# GPIOexpander_4.net
KiCad netlist of a schematic drawn in EAGLE
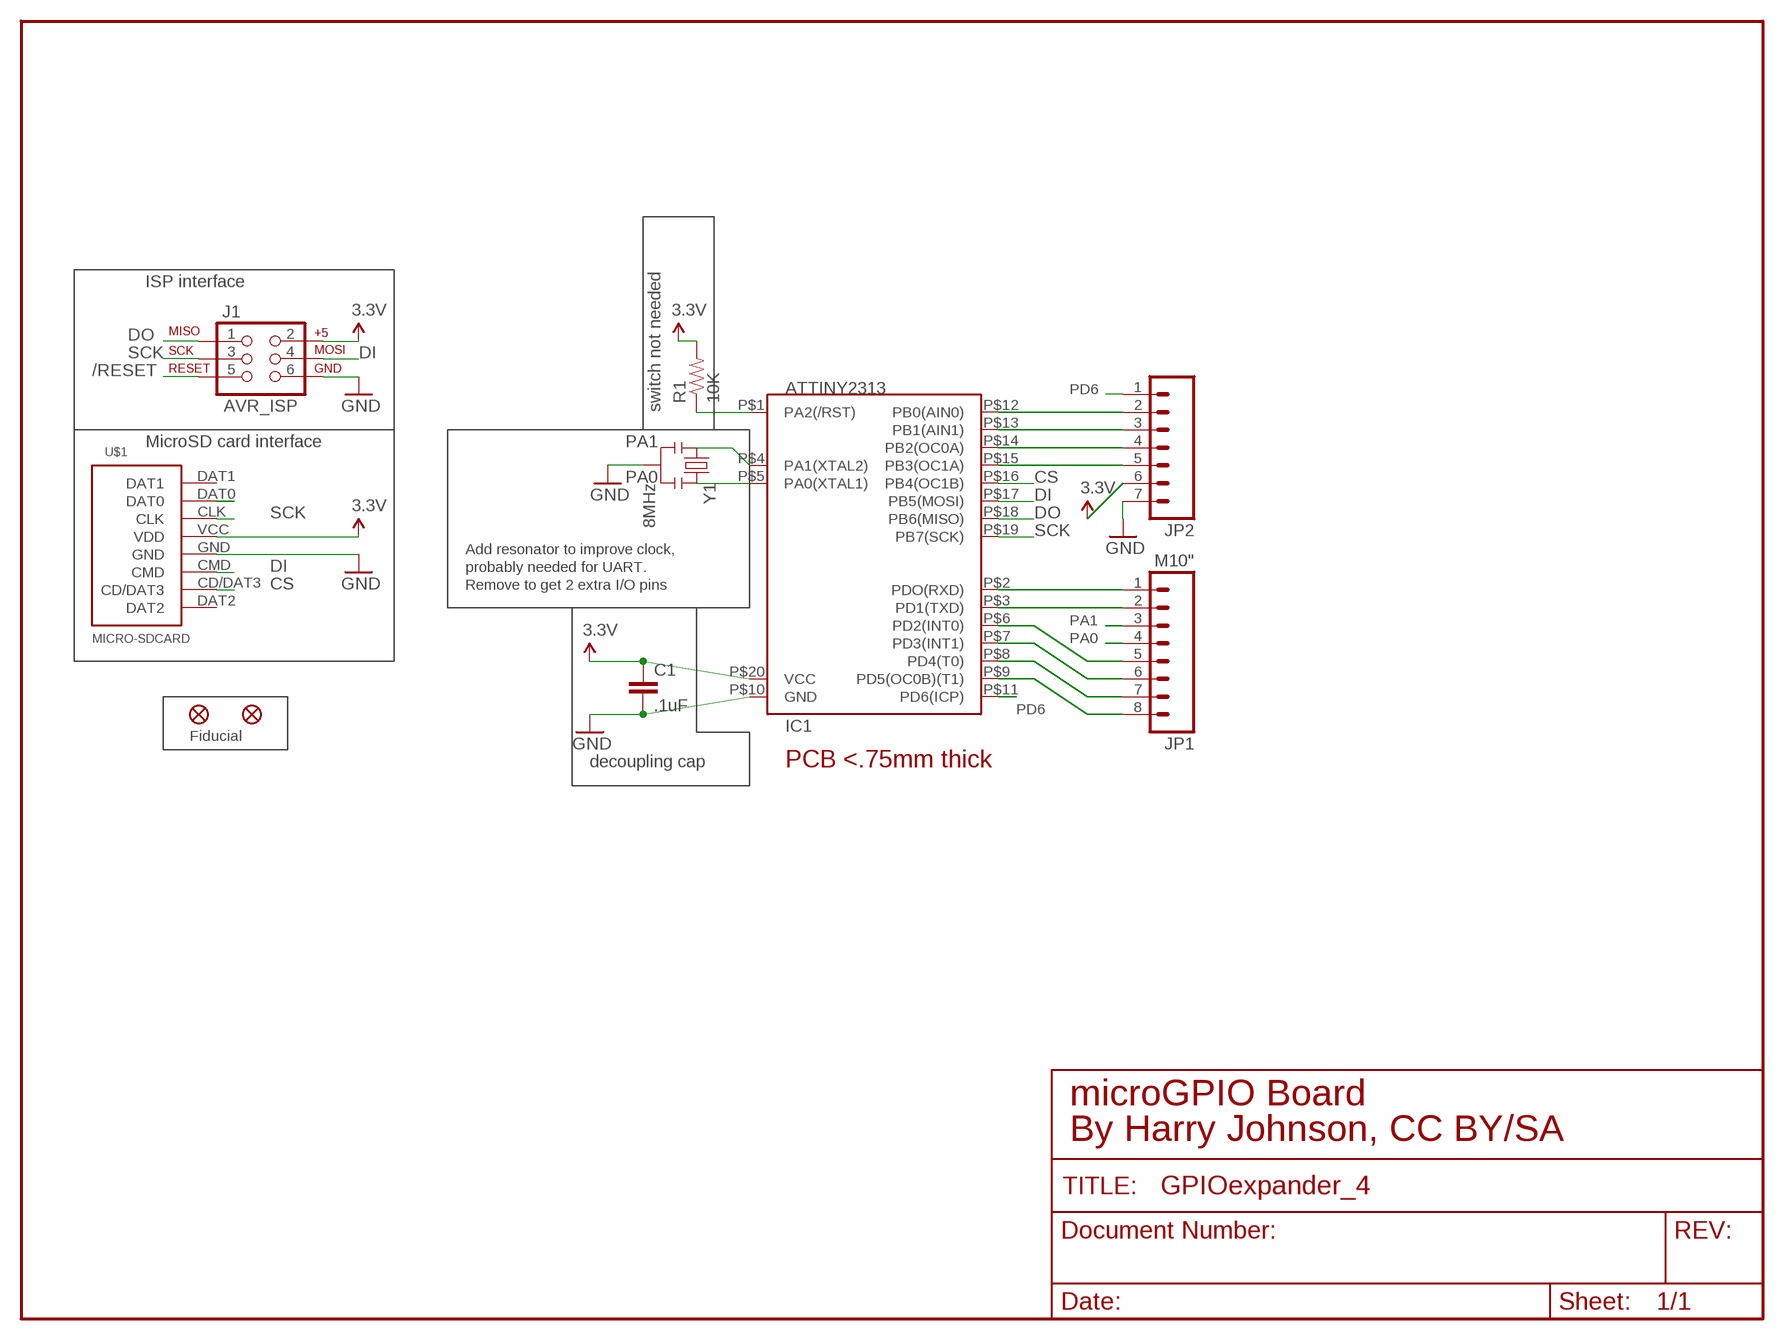
[diagram p0: schematic, sheet 1]

(export (version "E")
  (design (tool "Eeschema 10.0.6"))
  (components
    (comp (ref "C1")
      (value ".1uF")
      (footprint "eagle-import:0805")
      (libsource (lib "eagle-import") (part "CAP0805"))
    )
    (comp (ref "IC1")
      (value "ATTINY2313")
      (footprint "eagle-import:SO20W")
      (libsource (lib "eagle-import") (part "ATTINY2313SOIC"))
    )
    (comp (ref "J1")
      (value "AVR_ISP")
      (footprint "eagle-import:2X3-NS")
      (libsource (lib "eagle-import") (part "AVR_SPI_PRG_6NS"))
    )
    (comp (ref "JP1")
      (value "M10\"")
      (footprint "eagle-import:1X08")
      (libsource (lib "eagle-import") (part "M08"))
    )
    (comp (ref "JP2")
      (value "M07")
      (footprint "eagle-import:1X07")
      (libsource (lib "eagle-import") (part "M07"))
    )
    (comp (ref "R1")
      (value "10K")
      (footprint "eagle-import:0805")
      (libsource (lib "eagle-import") (part "RESISTOR"))
    )
    (comp (ref "U$1")
      (value "MICRO-SDCARD")
      (footprint "eagle-import:MICRO-SDCARD")
      (libsource (lib "eagle-import") (part "MICRO-SDCARD"))
    )
    (comp (ref "U$2")
      (value "FIDUCIAL1X2.5")
      (footprint "eagle-import:FIDUCIAL-1X2.5")
      (libsource (lib "eagle-import") (part "FIDUCIAL1X2.5"))
    )
    (comp (ref "U$3")
      (value "FIDUCIAL1X2.5")
      (footprint "eagle-import:FIDUCIAL-1X2.5")
      (libsource (lib "eagle-import") (part "FIDUCIAL1X2.5"))
    )
    (comp (ref "Y1")
      (value "8MHz")
      (footprint "eagle-import:RESONATOR-SMD")
      (libsource (lib "eagle-import") (part "RESONATORSMD"))
    )
  )
  (nets
    (net (code "1") (name "/CS") (class "Default")
      (node (ref "IC1") (pin "P$16") (pinfunction "PB4(OC1B)_P$16") (pintype "bidirectional"))
      (node (ref "U$1") (pin "CD/DAT3") (pinfunction "CD/DAT3_CD/DAT3") (pintype "bidirectional"))
    )
    (net (code "2") (name "/DI") (class "Default")
      (node (ref "IC1") (pin "P$17") (pinfunction "PB5(MOSI)_P$17") (pintype "bidirectional"))
      (node (ref "J1") (pin "4") (pinfunction "4_4") (pintype "passive"))
      (node (ref "U$1") (pin "CMD") (pinfunction "CMD_CMD") (pintype "bidirectional"))
    )
    (net (code "3") (name "/DO") (class "Default")
      (node (ref "IC1") (pin "P$18") (pinfunction "PB6(MISO)_P$18") (pintype "bidirectional"))
      (node (ref "J1") (pin "1") (pinfunction "1_1") (pintype "passive"))
      (node (ref "U$1") (pin "DAT0") (pinfunction "DAT0_DAT0") (pintype "bidirectional"))
    )
    (net (code "4") (name "/PA0") (class "Default")
      (node (ref "IC1") (pin "P$5") (pinfunction "PA0(XTAL1)_P$5") (pintype "bidirectional"))
      (node (ref "JP1") (pin "4") (pinfunction "4_4") (pintype "passive"))
      (node (ref "Y1") (pin "3") (pinfunction "3_3") (pintype "passive"))
    )
    (net (code "5") (name "/PA1") (class "Default")
      (node (ref "IC1") (pin "P$4") (pinfunction "PA1(XTAL2)_P$4") (pintype "bidirectional"))
      (node (ref "JP1") (pin "3") (pinfunction "3_3") (pintype "passive"))
      (node (ref "Y1") (pin "1") (pinfunction "1_1") (pintype "passive"))
    )
    (net (code "6") (name "/PD6") (class "Default")
      (node (ref "IC1") (pin "P$11") (pinfunction "PD6(ICP)_P$11") (pintype "bidirectional"))
      (node (ref "JP2") (pin "1") (pinfunction "1_1") (pintype "passive"))
    )
    (net (code "7") (name "/SCK") (class "Default")
      (node (ref "IC1") (pin "P$19") (pinfunction "PB7(SCK)_P$19") (pintype "bidirectional"))
      (node (ref "J1") (pin "3") (pinfunction "3_3") (pintype "passive"))
      (node (ref "U$1") (pin "CLK") (pinfunction "CLK_CLK") (pintype "bidirectional"))
    )
    (net (code "8") (name "/{slash}RESET") (class "Default")
      (node (ref "IC1") (pin "P$1") (pinfunction "PA2(/RST)_P$1") (pintype "bidirectional"))
      (node (ref "J1") (pin "5") (pinfunction "5_5") (pintype "passive"))
      (node (ref "R1") (pin "1") (pinfunction "1_1") (pintype "passive"))
    )
    (net (code "9") (name "3.3V") (class "Default")
      (node (ref "C1") (pin "1") (pinfunction "1_1") (pintype "passive"))
      (node (ref "IC1") (pin "P$20") (pinfunction "VCC_P$20") (pintype "bidirectional"))
      (node (ref "J1") (pin "2") (pinfunction "2_2") (pintype "passive"))
      (node (ref "JP2") (pin "6") (pinfunction "6_6") (pintype "passive"))
      (node (ref "R1") (pin "2") (pinfunction "2_2") (pintype "passive"))
      (node (ref "U$1") (pin "VCC") (pinfunction "VDD_VCC") (pintype "bidirectional"))
    )
    (net (code "10") (name "GND") (class "Default")
      (node (ref "C1") (pin "2") (pinfunction "2_2") (pintype "passive"))
      (node (ref "IC1") (pin "P$10") (pinfunction "GND_P$10") (pintype "bidirectional"))
      (node (ref "J1") (pin "6") (pinfunction "6_6") (pintype "passive"))
      (node (ref "JP2") (pin "7") (pinfunction "7_7") (pintype "passive"))
      (node (ref "U$1") (pin "GND") (pinfunction "GND_GND") (pintype "bidirectional"))
      (node (ref "Y1") (pin "2") (pinfunction "2_2") (pintype "passive"))
    )
    (net (code "11") (name "Net-(IC1-PB0(AIN0))") (class "Default")
      (node (ref "IC1") (pin "P$12") (pinfunction "PB0(AIN0)_P$12") (pintype "bidirectional"))
      (node (ref "JP2") (pin "2") (pinfunction "2_2") (pintype "passive"))
    )
    (net (code "12") (name "Net-(IC1-PB1(AIN1))") (class "Default")
      (node (ref "IC1") (pin "P$13") (pinfunction "PB1(AIN1)_P$13") (pintype "bidirectional"))
      (node (ref "JP2") (pin "3") (pinfunction "3_3") (pintype "passive"))
    )
    (net (code "13") (name "Net-(IC1-PB2(OC0A))") (class "Default")
      (node (ref "IC1") (pin "P$14") (pinfunction "PB2(OC0A)_P$14") (pintype "bidirectional"))
      (node (ref "JP2") (pin "4") (pinfunction "4_4") (pintype "passive"))
    )
    (net (code "14") (name "Net-(IC1-PB3(OC1A))") (class "Default")
      (node (ref "IC1") (pin "P$15") (pinfunction "PB3(OC1A)_P$15") (pintype "bidirectional"))
      (node (ref "JP2") (pin "5") (pinfunction "5_5") (pintype "passive"))
    )
    (net (code "15") (name "Net-(IC1-PD1(TXD))") (class "Default")
      (node (ref "IC1") (pin "P$3") (pinfunction "PD1(TXD)_P$3") (pintype "bidirectional"))
      (node (ref "JP1") (pin "2") (pinfunction "2_2") (pintype "passive"))
    )
    (net (code "16") (name "Net-(IC1-PD2(INT0))") (class "Default")
      (node (ref "IC1") (pin "P$6") (pinfunction "PD2(INT0)_P$6") (pintype "bidirectional"))
      (node (ref "JP1") (pin "5") (pinfunction "5_5") (pintype "passive"))
    )
    (net (code "17") (name "Net-(IC1-PD3(INT1))") (class "Default")
      (node (ref "IC1") (pin "P$7") (pinfunction "PD3(INT1)_P$7") (pintype "bidirectional"))
      (node (ref "JP1") (pin "6") (pinfunction "6_6") (pintype "passive"))
    )
    (net (code "18") (name "Net-(IC1-PD4(T0))") (class "Default")
      (node (ref "IC1") (pin "P$8") (pinfunction "PD4(T0)_P$8") (pintype "bidirectional"))
      (node (ref "JP1") (pin "7") (pinfunction "7_7") (pintype "passive"))
    )
    (net (code "19") (name "Net-(IC1-PD5(OC0B)(T1))") (class "Default")
      (node (ref "IC1") (pin "P$9") (pinfunction "PD5(OC0B)(T1)_P$9") (pintype "bidirectional"))
      (node (ref "JP1") (pin "8") (pinfunction "8_8") (pintype "passive"))
    )
    (net (code "20") (name "Net-(IC1-PDO(RXD))") (class "Default")
      (node (ref "IC1") (pin "P$2") (pinfunction "PDO(RXD)_P$2") (pintype "bidirectional"))
      (node (ref "JP1") (pin "1") (pinfunction "1_1") (pintype "passive"))
    )
    (net (code "21") (name "unconnected-(U$1-PadDAT1)") (class "Default")
      (node (ref "U$1") (pin "DAT1") (pinfunction "DAT1_DAT1") (pintype "bidirectional"))
    )
    (net (code "22") (name "unconnected-(U$1-PadDAT2)") (class "Default")
      (node (ref "U$1") (pin "DAT2") (pinfunction "DAT2_DAT2") (pintype "bidirectional"))
    )
  )
)
